# MUC.net
KiCad netlist of a schematic drawn in Altium Designer
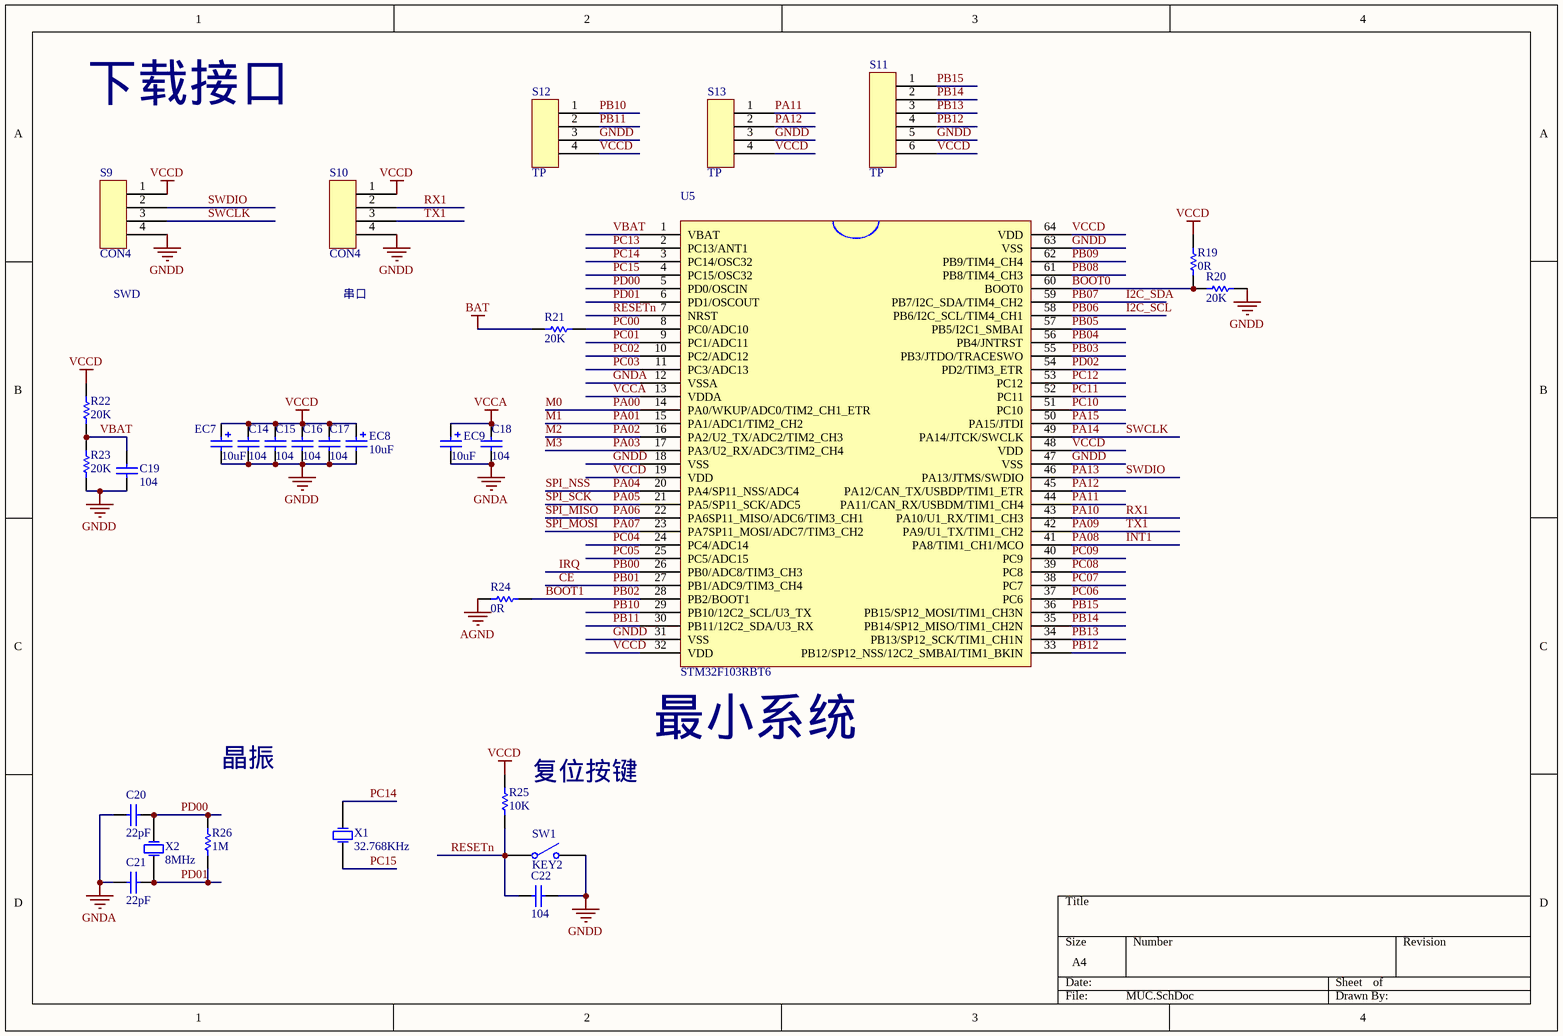
[diagram p0: MUC.SchDoc]

(export (version "E")
  (design (tool "Eeschema 10.0.6"))
  (components
    (comp (ref "C14") (value "104") (footprint "0603") (libsource (lib "yezi_sch") (part "CAP")))
    (comp (ref "C15") (value "104") (footprint "0603") (libsource (lib "yezi_sch") (part "CAP")))
    (comp (ref "C16") (value "104") (footprint "0603") (libsource (lib "yezi_sch") (part "CAP")))
    (comp (ref "C17") (value "104") (footprint "0603") (libsource (lib "yezi_sch") (part "CAP")))
    (comp (ref "C18") (value "104") (footprint "0603") (libsource (lib "yezi_sch") (part "CAP")))
    (comp (ref "C19") (value "104") (footprint "0603") (libsource (lib "yezi_sch") (part "CAP")))
    (comp (ref "C20") (value "22pF") (footprint "0805") (libsource (lib "yezi_sch") (part "CAP")))
    (comp (ref "C21") (value "22pF") (footprint "0805") (libsource (lib "yezi_sch") (part "CAP")))
    (comp (ref "C22") (value "104") (footprint "0603") (libsource (lib "yezi_sch") (part "CAP")))
    (comp (ref "EC7") (value "10uF") (footprint "1206") (libsource (lib "yezi_sch") (part "EC")))
    (comp (ref "EC8") (value "10uF") (footprint "1206") (libsource (lib "yezi_sch") (part "EC")))
    (comp (ref "EC9") (value "10uF") (footprint "1206") (libsource (lib "yezi_sch") (part "EC")))
    (comp (ref "R19") (value "0R") (footprint "0603") (libsource (lib "yezi_sch") (part "RES")))
    (comp (ref "R20") (value "20K") (footprint "0603") (libsource (lib "yezi_sch") (part "RES")))
    (comp (ref "R21") (value "20K") (footprint "0603") (libsource (lib "yezi_sch") (part "RES")))
    (comp (ref "R22") (value "20K") (footprint "0603") (libsource (lib "yezi_sch") (part "RES")))
    (comp (ref "R23") (value "20K") (footprint "0603") (libsource (lib "yezi_sch") (part "RES")))
    (comp (ref "R24") (value "0R") (footprint "0603") (libsource (lib "yezi_sch") (part "RES")))
    (comp (ref "R25") (value "10K") (footprint "0603") (libsource (lib "yezi_sch") (part "RES")))
    (comp (ref "R26") (value "1M") (footprint "0805") (libsource (lib "yezi_sch") (part "RES")))
    (comp (ref "S9") (value "CON4") (footprint "SIP4") (libsource (lib "yezi_sch") (part "CON4")))
    (comp (ref "S10") (value "CON4") (footprint "SIP4") (libsource (lib "yezi_sch") (part "CON4")))
    (comp (ref "S11") (value "TP") (footprint "TP6") (libsource (lib "yezi_sch") (part "CON6")))
    (comp (ref "S12") (value "TP") (footprint "TP4") (libsource (lib "yezi_sch") (part "CON4")))
    (comp (ref "S13") (value "TP") (footprint "TP4") (libsource (lib "yezi_sch") (part "CON4")))
    (comp (ref "SW1") (value "KEY2") (footprint "SSOP2N") (libsource (lib "yezi_sch") (part "KEY2")))
    (comp (ref "U5")
      (value "STM32F103RBT6")
      (footprint "TSQFP50P1200X1200X160-64N")
      (libsource (lib "yezi_sch") (part "STM32F103RBT6"))
    )
    (comp (ref "X1") (value "32.768KHz") (footprint "XTAL-50-2") (libsource (lib "yezi_sch") (part "XTAL")))
    (comp (ref "X2") (value "8MHz") (footprint "XTAL-200") (libsource (lib "yezi_sch") (part "XTAL")))
  )
  (nets
    (net (code "1") (name "/BOOT0") (class "Default")
      (node (ref "R19") (pin "1") (pinfunction "1_1") (pintype "passive"))
      (node (ref "R20") (pin "1") (pinfunction "1_1") (pintype "passive"))
      (node (ref "U5") (pin "60") (pinfunction "BOOT0_60") (pintype "passive"))
    )
    (net (code "2") (name "/BOOT1") (class "Default")
      (node (ref "R24") (pin "2") (pinfunction "2_2") (pintype "passive"))
      (node (ref "U5") (pin "28") (pinfunction "PB2/BOOT1_28") (pintype "passive"))
    )
    (net (code "3") (name "/CE") (class "Default")
      (node (ref "U5") (pin "27") (pinfunction "PB1/ADC9/TIM3_CH4_27") (pintype "passive"))
    )
    (net (code "4") (name "/I2C_SCL") (class "Default")
      (node (ref "U5") (pin "58") (pinfunction "PB6/I2C_SCL/TIM4_CH1_58") (pintype "passive"))
    )
    (net (code "5") (name "/I2C_SDA") (class "Default")
      (node (ref "U5") (pin "59") (pinfunction "PB7/I2C_SDA/TIM4_CH2_59") (pintype "passive"))
    )
    (net (code "6") (name "/INT1") (class "Default")
      (node (ref "U5") (pin "41") (pinfunction "PA8/TIM1_CH1/MCO_41") (pintype "passive"))
    )
    (net (code "7") (name "/IRQ") (class "Default")
      (node (ref "U5") (pin "26") (pinfunction "PB0/ADC8/TIM3_CH3_26") (pintype "passive"))
    )
    (net (code "8") (name "/M0") (class "Default")
      (node (ref "U5") (pin "14") (pinfunction "PA0/WKUP/ADC0/TIM2_CH1_ETR_14") (pintype "passive"))
    )
    (net (code "9") (name "/M1") (class "Default")
      (node (ref "U5") (pin "15") (pinfunction "PA1/ADC1/TIM2_CH2_15") (pintype "passive"))
    )
    (net (code "10") (name "/M2") (class "Default")
      (node (ref "U5") (pin "16") (pinfunction "PA2/U2_TX/ADC2/TIM2_CH3_16") (pintype "passive"))
    )
    (net (code "11") (name "/M3") (class "Default")
      (node (ref "U5") (pin "17") (pinfunction "PA3/U2_RX/ADC3/TIM2_CH4_17") (pintype "passive"))
    )
    (net (code "12") (name "/PA04") (class "Default")
      (node (ref "U5") (pin "20") (pinfunction "PA4/SP11_NSS/ADC4_20") (pintype "passive"))
    )
    (net (code "13") (name "/PA05") (class "Default")
      (node (ref "U5") (pin "21") (pinfunction "PA5/SP11_SCK/ADC5_21") (pintype "passive"))
    )
    (net (code "14") (name "/PA06") (class "Default")
      (node (ref "U5") (pin "22") (pinfunction "PA6SP11_MISO/ADC6/TIM3_CH1_22") (pintype "passive"))
    )
    (net (code "15") (name "/PA07") (class "Default")
      (node (ref "U5") (pin "23") (pinfunction "PA7SP11_MOSI/ADC7/TIM3_CH2_23") (pintype "passive"))
    )
    (net (code "16") (name "/PA09") (class "Default")
      (node (ref "S10") (pin "3") (pinfunction "3_3") (pintype "passive"))
      (node (ref "U5") (pin "42") (pinfunction "PA9/U1_TX/TIM1_CH2_42") (pintype "passive"))
    )
    (net (code "17") (name "/PA10") (class "Default")
      (node (ref "S10") (pin "2") (pinfunction "2_2") (pintype "passive"))
      (node (ref "U5") (pin "43") (pinfunction "PA10/U1_RX/TIM1_CH3_43") (pintype "passive"))
    )
    (net (code "18") (name "/PA11") (class "Default")
      (node (ref "S13") (pin "1") (pinfunction "1_1") (pintype "passive"))
      (node (ref "U5") (pin "44") (pinfunction "PA11/CAN_RX/USBDM/TIM1_CH4_44") (pintype "passive"))
    )
    (net (code "19") (name "/PA12") (class "Default")
      (node (ref "S13") (pin "2") (pinfunction "2_2") (pintype "passive"))
      (node (ref "U5") (pin "45") (pinfunction "PA12/CAN_TX/USBDP/TIM1_ETR_45") (pintype "passive"))
    )
    (net (code "20") (name "/PA13") (class "Default")
      (node (ref "S9") (pin "2") (pinfunction "2_2") (pintype "passive"))
      (node (ref "U5") (pin "46") (pinfunction "PA13/JTMS/SWDIO_46") (pintype "passive"))
    )
    (net (code "21") (name "/PA14") (class "Default")
      (node (ref "S9") (pin "3") (pinfunction "3_3") (pintype "passive"))
      (node (ref "U5") (pin "49") (pinfunction "PA14/JTCK/SWCLK_49") (pintype "passive"))
    )
    (net (code "22") (name "/PA15") (class "Default")
      (node (ref "U5") (pin "50") (pinfunction "PA15/JTDI_50") (pintype "passive"))
    )
    (net (code "23") (name "/PB03") (class "Default")
      (node (ref "U5") (pin "55") (pinfunction "PB3/JTDO/TRACESWO_55") (pintype "passive"))
    )
    (net (code "24") (name "/PB04") (class "Default")
      (node (ref "U5") (pin "56") (pinfunction "PB4/JNTRST_56") (pintype "passive"))
    )
    (net (code "25") (name "/PB05") (class "Default")
      (node (ref "U5") (pin "57") (pinfunction "PB5/I2C1_SMBAI_57") (pintype "passive"))
    )
    (net (code "26") (name "/PB08") (class "Default")
      (node (ref "U5") (pin "61") (pinfunction "PB8/TIM4_CH3_61") (pintype "passive"))
    )
    (net (code "27") (name "/PB09") (class "Default")
      (node (ref "U5") (pin "62") (pinfunction "PB9/TIM4_CH4_62") (pintype "passive"))
    )
    (net (code "28") (name "/PB10") (class "Default")
      (node (ref "S12") (pin "1") (pinfunction "1_1") (pintype "passive"))
      (node (ref "U5") (pin "29") (pinfunction "PB10/12C2_SCL/U3_TX_29") (pintype "passive"))
    )
    (net (code "29") (name "/PB11") (class "Default")
      (node (ref "S12") (pin "2") (pinfunction "2_2") (pintype "passive"))
      (node (ref "U5") (pin "30") (pinfunction "PB11/12C2_SDA/U3_RX_30") (pintype "passive"))
    )
    (net (code "30") (name "/PB12") (class "Default")
      (node (ref "S11") (pin "4") (pinfunction "4_4") (pintype "passive"))
      (node (ref "U5") (pin "33") (pinfunction "PB12/SP12_NSS/12C2_SMBAI/TIM1_BKIN_33") (pintype "passive"))
    )
    (net (code "31") (name "/PB13") (class "Default")
      (node (ref "S11") (pin "3") (pinfunction "3_3") (pintype "passive"))
      (node (ref "U5") (pin "34") (pinfunction "PB13/SP12_SCK/TIM1_CH1N_34") (pintype "passive"))
    )
    (net (code "32") (name "/PB14") (class "Default")
      (node (ref "S11") (pin "2") (pinfunction "2_2") (pintype "passive"))
      (node (ref "U5") (pin "35") (pinfunction "PB14/SP12_MISO/TIM1_CH2N_35") (pintype "passive"))
    )
    (net (code "33") (name "/PB15") (class "Default")
      (node (ref "S11") (pin "1") (pinfunction "1_1") (pintype "passive"))
      (node (ref "U5") (pin "36") (pinfunction "PB15/SP12_MOSI/TIM1_CH3N_36") (pintype "passive"))
    )
    (net (code "34") (name "/PC00") (class "Default")
      (node (ref "R21") (pin "2") (pinfunction "2_2") (pintype "passive"))
      (node (ref "U5") (pin "8") (pinfunction "PC0/ADC10_8") (pintype "passive"))
    )
    (net (code "35") (name "/PC01") (class "Default")
      (node (ref "U5") (pin "9") (pinfunction "PC1/ADC11_9") (pintype "passive"))
    )
    (net (code "36") (name "/PC02") (class "Default")
      (node (ref "U5") (pin "10") (pinfunction "PC2/ADC12_10") (pintype "passive"))
    )
    (net (code "37") (name "/PC03") (class "Default")
      (node (ref "U5") (pin "11") (pinfunction "PC3/ADC13_11") (pintype "passive"))
    )
    (net (code "38") (name "/PC04") (class "Default")
      (node (ref "U5") (pin "24") (pinfunction "PC4/ADC14_24") (pintype "passive"))
    )
    (net (code "39") (name "/PC05") (class "Default")
      (node (ref "U5") (pin "25") (pinfunction "PC5/ADC15_25") (pintype "passive"))
    )
    (net (code "40") (name "/PC06") (class "Default")
      (node (ref "U5") (pin "37") (pinfunction "PC6_37") (pintype "passive"))
    )
    (net (code "41") (name "/PC07") (class "Default")
      (node (ref "U5") (pin "38") (pinfunction "PC7_38") (pintype "passive"))
    )
    (net (code "42") (name "/PC08") (class "Default")
      (node (ref "U5") (pin "39") (pinfunction "PC8_39") (pintype "passive"))
    )
    (net (code "43") (name "/PC09") (class "Default")
      (node (ref "U5") (pin "40") (pinfunction "PC9_40") (pintype "passive"))
    )
    (net (code "44") (name "/PC10") (class "Default")
      (node (ref "U5") (pin "51") (pinfunction "PC10_51") (pintype "passive"))
    )
    (net (code "45") (name "/PC11") (class "Default")
      (node (ref "U5") (pin "52") (pinfunction "PC11_52") (pintype "passive"))
    )
    (net (code "46") (name "/PC12") (class "Default")
      (node (ref "U5") (pin "53") (pinfunction "PC12_53") (pintype "passive"))
    )
    (net (code "47") (name "/PC13") (class "Default")
      (node (ref "U5") (pin "2") (pinfunction "PC13/ANT1_2") (pintype "passive"))
    )
    (net (code "48") (name "/PC14") (class "Default")
      (node (ref "U5") (pin "3") (pinfunction "PC14/OSC32_3") (pintype "passive"))
      (node (ref "X1") (pin "2") (pinfunction "OSC2_2") (pintype "passive"))
    )
    (net (code "49") (name "/PC15") (class "Default")
      (node (ref "U5") (pin "4") (pinfunction "PC15/OSC32_4") (pintype "passive"))
      (node (ref "X1") (pin "1") (pinfunction "OSC1_1") (pintype "passive"))
    )
    (net (code "50") (name "/PD00") (class "Default")
      (node (ref "C20") (pin "2") (pinfunction "2_2") (pintype "passive"))
      (node (ref "R26") (pin "2") (pinfunction "2_2") (pintype "passive"))
      (node (ref "U5") (pin "5") (pinfunction "PD0/OSCIN_5") (pintype "passive"))
      (node (ref "X2") (pin "2") (pinfunction "OSC2_2") (pintype "passive"))
    )
    (net (code "51") (name "/PD01") (class "Default")
      (node (ref "C21") (pin "2") (pinfunction "2_2") (pintype "passive"))
      (node (ref "R26") (pin "1") (pinfunction "1_1") (pintype "passive"))
      (node (ref "U5") (pin "6") (pinfunction "PD1/OSCOUT_6") (pintype "passive"))
      (node (ref "X2") (pin "1") (pinfunction "OSC1_1") (pintype "passive"))
    )
    (net (code "52") (name "/PD02") (class "Default")
      (node (ref "U5") (pin "54") (pinfunction "PD2/TIM3_ETR_54") (pintype "passive"))
    )
    (net (code "53") (name "/RESETn") (class "Default")
      (node (ref "C22") (pin "1") (pinfunction "1_1") (pintype "passive"))
      (node (ref "R25") (pin "1") (pinfunction "1_1") (pintype "passive"))
      (node (ref "SW1") (pin "1") (pinfunction "COMMON1_1") (pintype "passive"))
      (node (ref "U5") (pin "7") (pinfunction "NRST_7") (pintype "passive"))
    )
    (net (code "54") (name "/VBAT") (class "Default")
      (node (ref "C19") (pin "2") (pinfunction "2_2") (pintype "passive"))
      (node (ref "R22") (pin "1") (pinfunction "1_1") (pintype "passive"))
      (node (ref "R23") (pin "2") (pinfunction "2_2") (pintype "passive"))
      (node (ref "U5") (pin "1") (pinfunction "VBAT_1") (pintype "passive"))
    )
    (net (code "55") (name "AGND") (class "Default")
      (node (ref "R24") (pin "1") (pinfunction "1_1") (pintype "passive"))
    )
    (net (code "56") (name "BAT") (class "Default")
      (node (ref "R21") (pin "1") (pinfunction "1_1") (pintype "passive"))
    )
    (net (code "57") (name "GNDA") (class "Default")
      (node (ref "C18") (pin "1") (pinfunction "1_1") (pintype "passive"))
      (node (ref "C20") (pin "1") (pinfunction "1_1") (pintype "passive"))
      (node (ref "C21") (pin "1") (pinfunction "1_1") (pintype "passive"))
      (node (ref "EC9") (pin "2") (pinfunction "2_2") (pintype "passive"))
      (node (ref "U5") (pin "12") (pinfunction "VSSA_12") (pintype "passive"))
    )
    (net (code "58") (name "GNDD") (class "Default")
      (node (ref "C14") (pin "1") (pinfunction "1_1") (pintype "passive"))
      (node (ref "C15") (pin "1") (pinfunction "1_1") (pintype "passive"))
      (node (ref "C16") (pin "1") (pinfunction "1_1") (pintype "passive"))
      (node (ref "C17") (pin "1") (pinfunction "1_1") (pintype "passive"))
      (node (ref "C19") (pin "1") (pinfunction "1_1") (pintype "passive"))
      (node (ref "C22") (pin "2") (pinfunction "2_2") (pintype "passive"))
      (node (ref "EC7") (pin "2") (pinfunction "2_2") (pintype "passive"))
      (node (ref "EC8") (pin "2") (pinfunction "2_2") (pintype "passive"))
      (node (ref "R20") (pin "2") (pinfunction "2_2") (pintype "passive"))
      (node (ref "R23") (pin "1") (pinfunction "1_1") (pintype "passive"))
      (node (ref "S10") (pin "4") (pinfunction "4_4") (pintype "passive"))
      (node (ref "S11") (pin "5") (pinfunction "5_5") (pintype "passive"))
      (node (ref "S12") (pin "3") (pinfunction "3_3") (pintype "passive"))
      (node (ref "S13") (pin "3") (pinfunction "3_3") (pintype "passive"))
      (node (ref "S9") (pin "4") (pinfunction "4_4") (pintype "passive"))
      (node (ref "SW1") (pin "2") (pinfunction "NO1_2") (pintype "passive"))
      (node (ref "U5") (pin "18") (pinfunction "VSS_18") (pintype "passive"))
      (node (ref "U5") (pin "31") (pinfunction "VSS_31") (pintype "passive"))
      (node (ref "U5") (pin "47") (pinfunction "VSS_47") (pintype "passive"))
      (node (ref "U5") (pin "63") (pinfunction "VSS_63") (pintype "passive"))
    )
    (net (code "59") (name "VCCA") (class "Default")
      (node (ref "C18") (pin "2") (pinfunction "2_2") (pintype "passive"))
      (node (ref "EC9") (pin "1") (pinfunction "1_1") (pintype "passive"))
      (node (ref "U5") (pin "13") (pinfunction "VDDA_13") (pintype "passive"))
    )
    (net (code "60") (name "VCCD") (class "Default")
      (node (ref "C14") (pin "2") (pinfunction "2_2") (pintype "passive"))
      (node (ref "C15") (pin "2") (pinfunction "2_2") (pintype "passive"))
      (node (ref "C16") (pin "2") (pinfunction "2_2") (pintype "passive"))
      (node (ref "C17") (pin "2") (pinfunction "2_2") (pintype "passive"))
      (node (ref "EC7") (pin "1") (pinfunction "1_1") (pintype "passive"))
      (node (ref "EC8") (pin "1") (pinfunction "1_1") (pintype "passive"))
      (node (ref "R19") (pin "2") (pinfunction "2_2") (pintype "passive"))
      (node (ref "R22") (pin "2") (pinfunction "2_2") (pintype "passive"))
      (node (ref "R25") (pin "2") (pinfunction "2_2") (pintype "passive"))
      (node (ref "S10") (pin "1") (pinfunction "1_1") (pintype "passive"))
      (node (ref "S11") (pin "6") (pinfunction "6_6") (pintype "passive"))
      (node (ref "S12") (pin "4") (pinfunction "4_4") (pintype "passive"))
      (node (ref "S13") (pin "4") (pinfunction "4_4") (pintype "passive"))
      (node (ref "S9") (pin "1") (pinfunction "1_1") (pintype "passive"))
      (node (ref "U5") (pin "19") (pinfunction "VDD_19") (pintype "passive"))
      (node (ref "U5") (pin "32") (pinfunction "VDD_32") (pintype "passive"))
      (node (ref "U5") (pin "48") (pinfunction "VDD_48") (pintype "passive"))
      (node (ref "U5") (pin "64") (pinfunction "VDD_64") (pintype "passive"))
    )
  )
)
